# AND_1_1.net
KiCad netlist of a schematic drawn in EAGLE
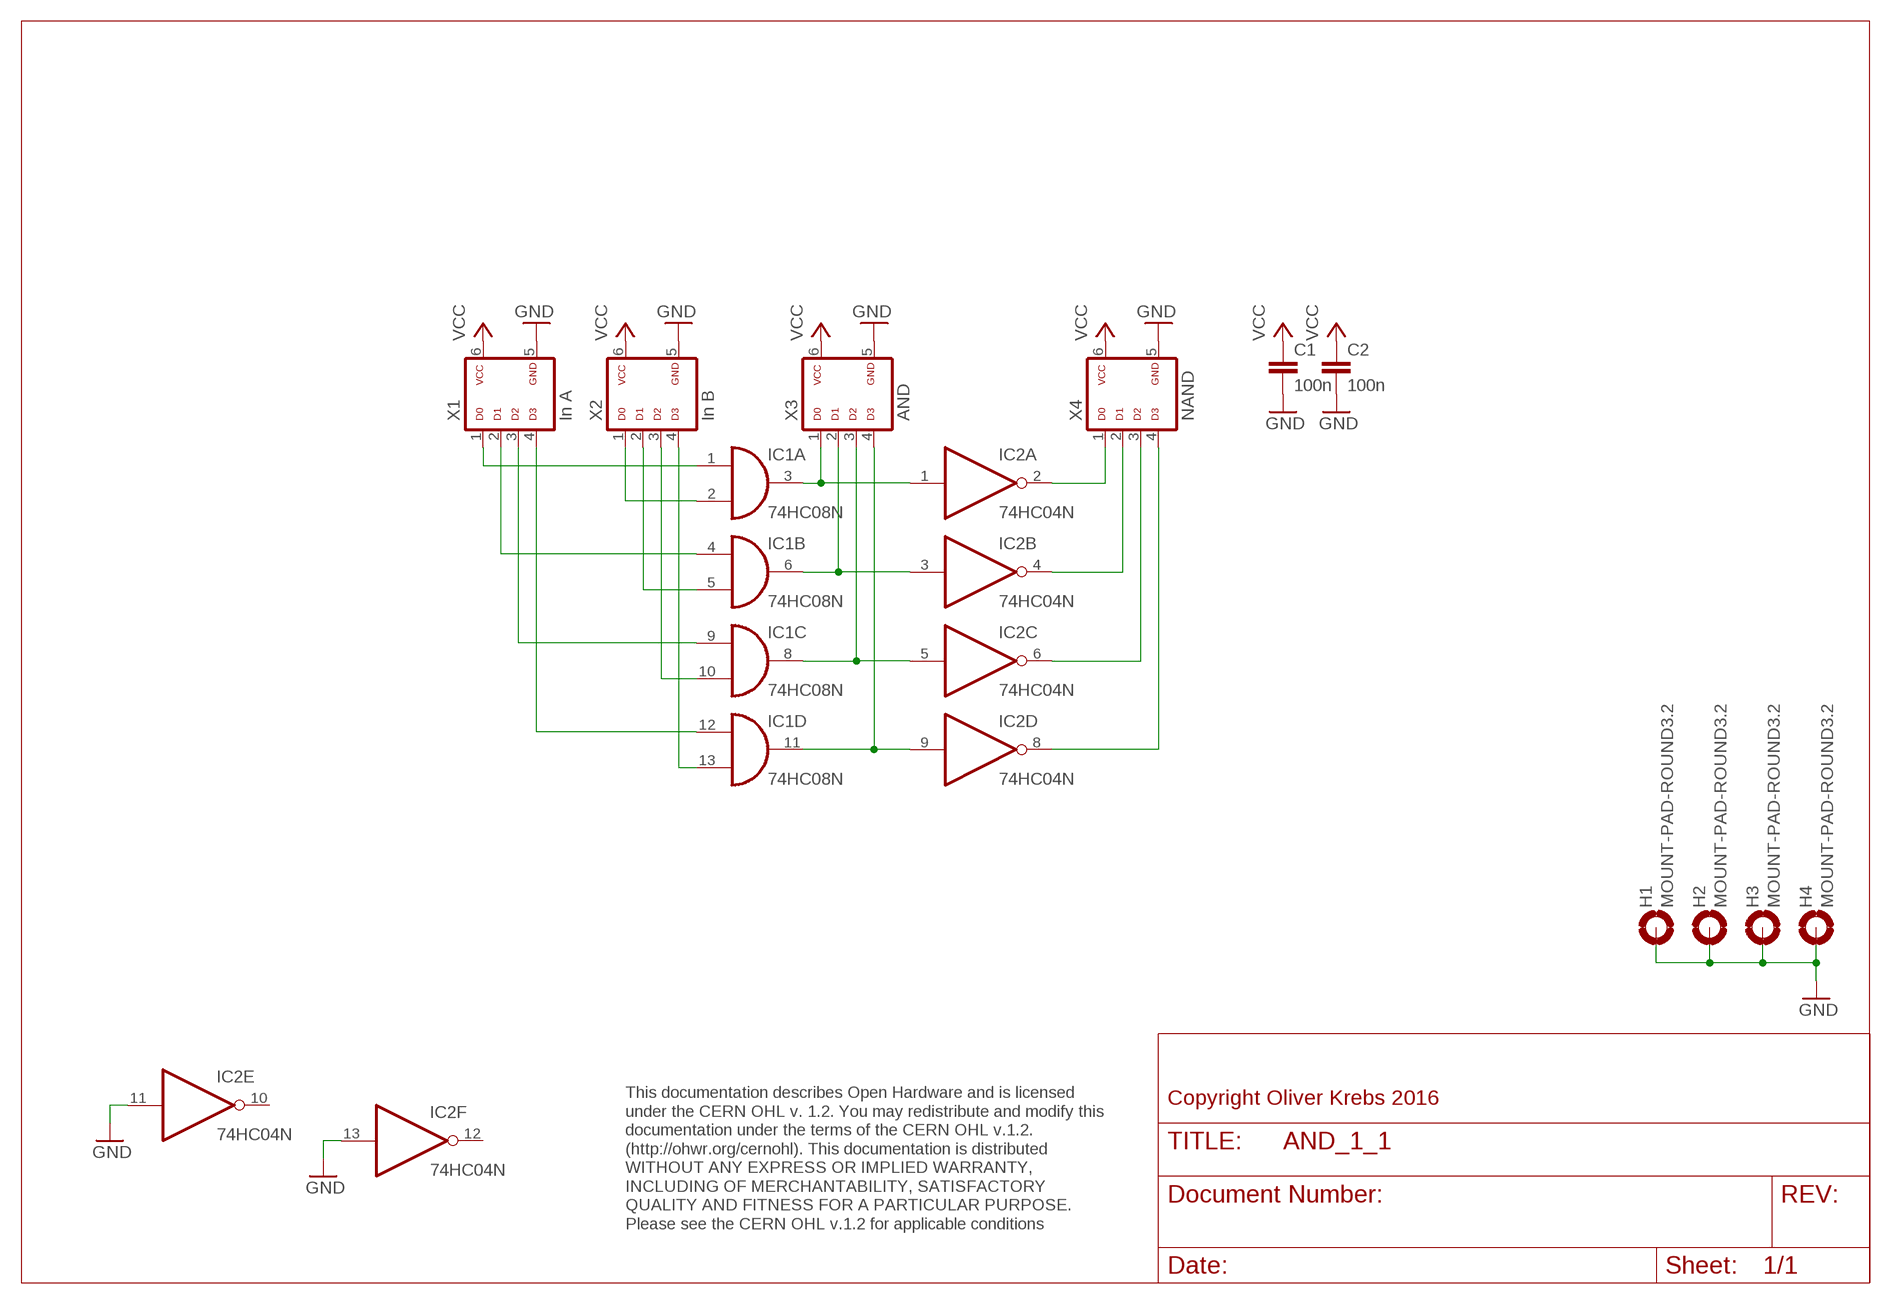
[diagram p0: schematic, sheet 1]

(export (version "E")
  (design (tool "Eeschema 10.0.6"))
  (components
    (comp (ref "C1")
      (value "100n")
      (footprint "eagle-import:C050-025X075")
      (libsource (lib "eagle-import") (part "C-EU050-025X075"))
    )
    (comp (ref "C2")
      (value "100n")
      (footprint "eagle-import:C050-025X075")
      (libsource (lib "eagle-import") (part "C-EU050-025X075"))
    )
    (comp (ref "H1")
      (value "MOUNT-PAD-ROUND3.2")
      (footprint "eagle-import:3,2-PAD")
      (libsource (lib "eagle-import") (part "MOUNT-PAD-ROUND3.2"))
    )
    (comp (ref "H2")
      (value "MOUNT-PAD-ROUND3.2")
      (footprint "eagle-import:3,2-PAD")
      (libsource (lib "eagle-import") (part "MOUNT-PAD-ROUND3.2"))
    )
    (comp (ref "H3")
      (value "MOUNT-PAD-ROUND3.2")
      (footprint "eagle-import:3,2-PAD")
      (libsource (lib "eagle-import") (part "MOUNT-PAD-ROUND3.2"))
    )
    (comp (ref "H4")
      (value "MOUNT-PAD-ROUND3.2")
      (footprint "eagle-import:3,2-PAD")
      (libsource (lib "eagle-import") (part "MOUNT-PAD-ROUND3.2"))
    )
    (comp (ref "IC1")
      (value "74HC08N")
      (footprint "eagle-import:DIL14")
      (libsource (lib "eagle-import") (part "7408NHC"))
    )
    (comp (ref "IC2")
      (value "74HC04N")
      (footprint "eagle-import:DIL14")
      (libsource (lib "eagle-import") (part "7404NHC"))
    )
    (comp (ref "X1")
      (value "In A")
      (footprint "eagle-import:ML-6")
      (libsource (lib "eagle-import") (part "ML6D"))
    )
    (comp (ref "X2")
      (value "In B")
      (footprint "eagle-import:ML-6")
      (libsource (lib "eagle-import") (part "ML6D"))
    )
    (comp (ref "X3")
      (value "AND")
      (footprint "eagle-import:ML-6")
      (libsource (lib "eagle-import") (part "ML6D"))
    )
    (comp (ref "X4")
      (value "NAND")
      (footprint "eagle-import:ML-6")
      (libsource (lib "eagle-import") (part "ML6D"))
    )
  )
  (nets
    (net (code "1") (name "GND") (class "Default")
      (node (ref "C1") (pin "2") (pinfunction "2_2") (pintype "passive"))
      (node (ref "C2") (pin "2") (pinfunction "2_2") (pintype "passive"))
      (node (ref "H1") (pin "B3,2") (pinfunction "MOUNT_B3,2") (pintype "passive"))
      (node (ref "H2") (pin "B3,2") (pinfunction "MOUNT_B3,2") (pintype "passive"))
      (node (ref "H3") (pin "B3,2") (pinfunction "MOUNT_B3,2") (pintype "passive"))
      (node (ref "H4") (pin "B3,2") (pinfunction "MOUNT_B3,2") (pintype "passive"))
      (node (ref "IC2") (pin "11") (pinfunction "I_11") (pintype "input"))
      (node (ref "IC2") (pin "13") (pinfunction "I_13") (pintype "input"))
      (node (ref "X1") (pin "5") (pinfunction "5_5") (pintype "passive"))
      (node (ref "X2") (pin "5") (pinfunction "5_5") (pintype "passive"))
      (node (ref "X3") (pin "5") (pinfunction "5_5") (pintype "passive"))
      (node (ref "X4") (pin "5") (pinfunction "5_5") (pintype "passive"))
    )
    (net (code "2") (name "Net-(IC1A-I0)") (class "Default")
      (node (ref "IC1") (pin "1") (pinfunction "I0_1") (pintype "input"))
      (node (ref "X1") (pin "1") (pinfunction "1_1") (pintype "passive"))
    )
    (net (code "3") (name "Net-(IC1A-I1)") (class "Default")
      (node (ref "IC1") (pin "2") (pinfunction "I1_2") (pintype "input"))
      (node (ref "X2") (pin "1") (pinfunction "1_1") (pintype "passive"))
    )
    (net (code "4") (name "Net-(IC1A-O)") (class "Default")
      (node (ref "IC1") (pin "3") (pinfunction "O_3") (pintype "output"))
      (node (ref "IC2") (pin "1") (pinfunction "I_1") (pintype "input"))
      (node (ref "X3") (pin "1") (pinfunction "1_1") (pintype "passive"))
    )
    (net (code "5") (name "Net-(IC1B-I0)") (class "Default")
      (node (ref "IC1") (pin "4") (pinfunction "I0_4") (pintype "input"))
      (node (ref "X1") (pin "2") (pinfunction "2_2") (pintype "passive"))
    )
    (net (code "6") (name "Net-(IC1B-I1)") (class "Default")
      (node (ref "IC1") (pin "5") (pinfunction "I1_5") (pintype "input"))
      (node (ref "X2") (pin "2") (pinfunction "2_2") (pintype "passive"))
    )
    (net (code "7") (name "Net-(IC1B-O)") (class "Default")
      (node (ref "IC1") (pin "6") (pinfunction "O_6") (pintype "output"))
      (node (ref "IC2") (pin "3") (pinfunction "I_3") (pintype "input"))
      (node (ref "X3") (pin "2") (pinfunction "2_2") (pintype "passive"))
    )
    (net (code "8") (name "Net-(IC1C-I0)") (class "Default")
      (node (ref "IC1") (pin "9") (pinfunction "I0_9") (pintype "input"))
      (node (ref "X1") (pin "3") (pinfunction "3_3") (pintype "passive"))
    )
    (net (code "9") (name "Net-(IC1C-I1)") (class "Default")
      (node (ref "IC1") (pin "10") (pinfunction "I1_10") (pintype "input"))
      (node (ref "X2") (pin "3") (pinfunction "3_3") (pintype "passive"))
    )
    (net (code "10") (name "Net-(IC1C-O)") (class "Default")
      (node (ref "IC1") (pin "8") (pinfunction "O_8") (pintype "output"))
      (node (ref "IC2") (pin "5") (pinfunction "I_5") (pintype "input"))
      (node (ref "X3") (pin "3") (pinfunction "3_3") (pintype "passive"))
    )
    (net (code "11") (name "Net-(IC1D-I0)") (class "Default")
      (node (ref "IC1") (pin "12") (pinfunction "I0_12") (pintype "input"))
      (node (ref "X1") (pin "4") (pinfunction "4_4") (pintype "passive"))
    )
    (net (code "12") (name "Net-(IC1D-I1)") (class "Default")
      (node (ref "IC1") (pin "13") (pinfunction "I1_13") (pintype "input"))
      (node (ref "X2") (pin "4") (pinfunction "4_4") (pintype "passive"))
    )
    (net (code "13") (name "Net-(IC1D-O)") (class "Default")
      (node (ref "IC1") (pin "11") (pinfunction "O_11") (pintype "output"))
      (node (ref "IC2") (pin "9") (pinfunction "I_9") (pintype "input"))
      (node (ref "X3") (pin "4") (pinfunction "4_4") (pintype "passive"))
    )
    (net (code "14") (name "Net-(IC2A-O)") (class "Default")
      (node (ref "IC2") (pin "2") (pinfunction "O_2") (pintype "output"))
      (node (ref "X4") (pin "1") (pinfunction "1_1") (pintype "passive"))
    )
    (net (code "15") (name "Net-(IC2B-O)") (class "Default")
      (node (ref "IC2") (pin "4") (pinfunction "O_4") (pintype "output"))
      (node (ref "X4") (pin "2") (pinfunction "2_2") (pintype "passive"))
    )
    (net (code "16") (name "Net-(IC2C-O)") (class "Default")
      (node (ref "IC2") (pin "6") (pinfunction "O_6") (pintype "output"))
      (node (ref "X4") (pin "3") (pinfunction "3_3") (pintype "passive"))
    )
    (net (code "17") (name "Net-(IC2D-O)") (class "Default")
      (node (ref "IC2") (pin "8") (pinfunction "O_8") (pintype "output"))
      (node (ref "X4") (pin "4") (pinfunction "4_4") (pintype "passive"))
    )
    (net (code "18") (name "VCC") (class "Default")
      (node (ref "C1") (pin "1") (pinfunction "1_1") (pintype "passive"))
      (node (ref "C2") (pin "1") (pinfunction "1_1") (pintype "passive"))
      (node (ref "X1") (pin "6") (pinfunction "6_6") (pintype "passive"))
      (node (ref "X2") (pin "6") (pinfunction "6_6") (pintype "passive"))
      (node (ref "X3") (pin "6") (pinfunction "6_6") (pintype "passive"))
      (node (ref "X4") (pin "6") (pinfunction "6_6") (pintype "passive"))
    )
    (net (code "19") (name "unconnected-(IC2E-O-Pad10)") (class "Default")
      (node (ref "IC2") (pin "10") (pinfunction "O_10") (pintype "output"))
    )
    (net (code "20") (name "unconnected-(IC2F-O-Pad12)") (class "Default")
      (node (ref "IC2") (pin "12") (pinfunction "O_12") (pintype "output"))
    )
  )
)
